# ATU_MCU.net
KiCad netlist of a schematic drawn in Altium Designer
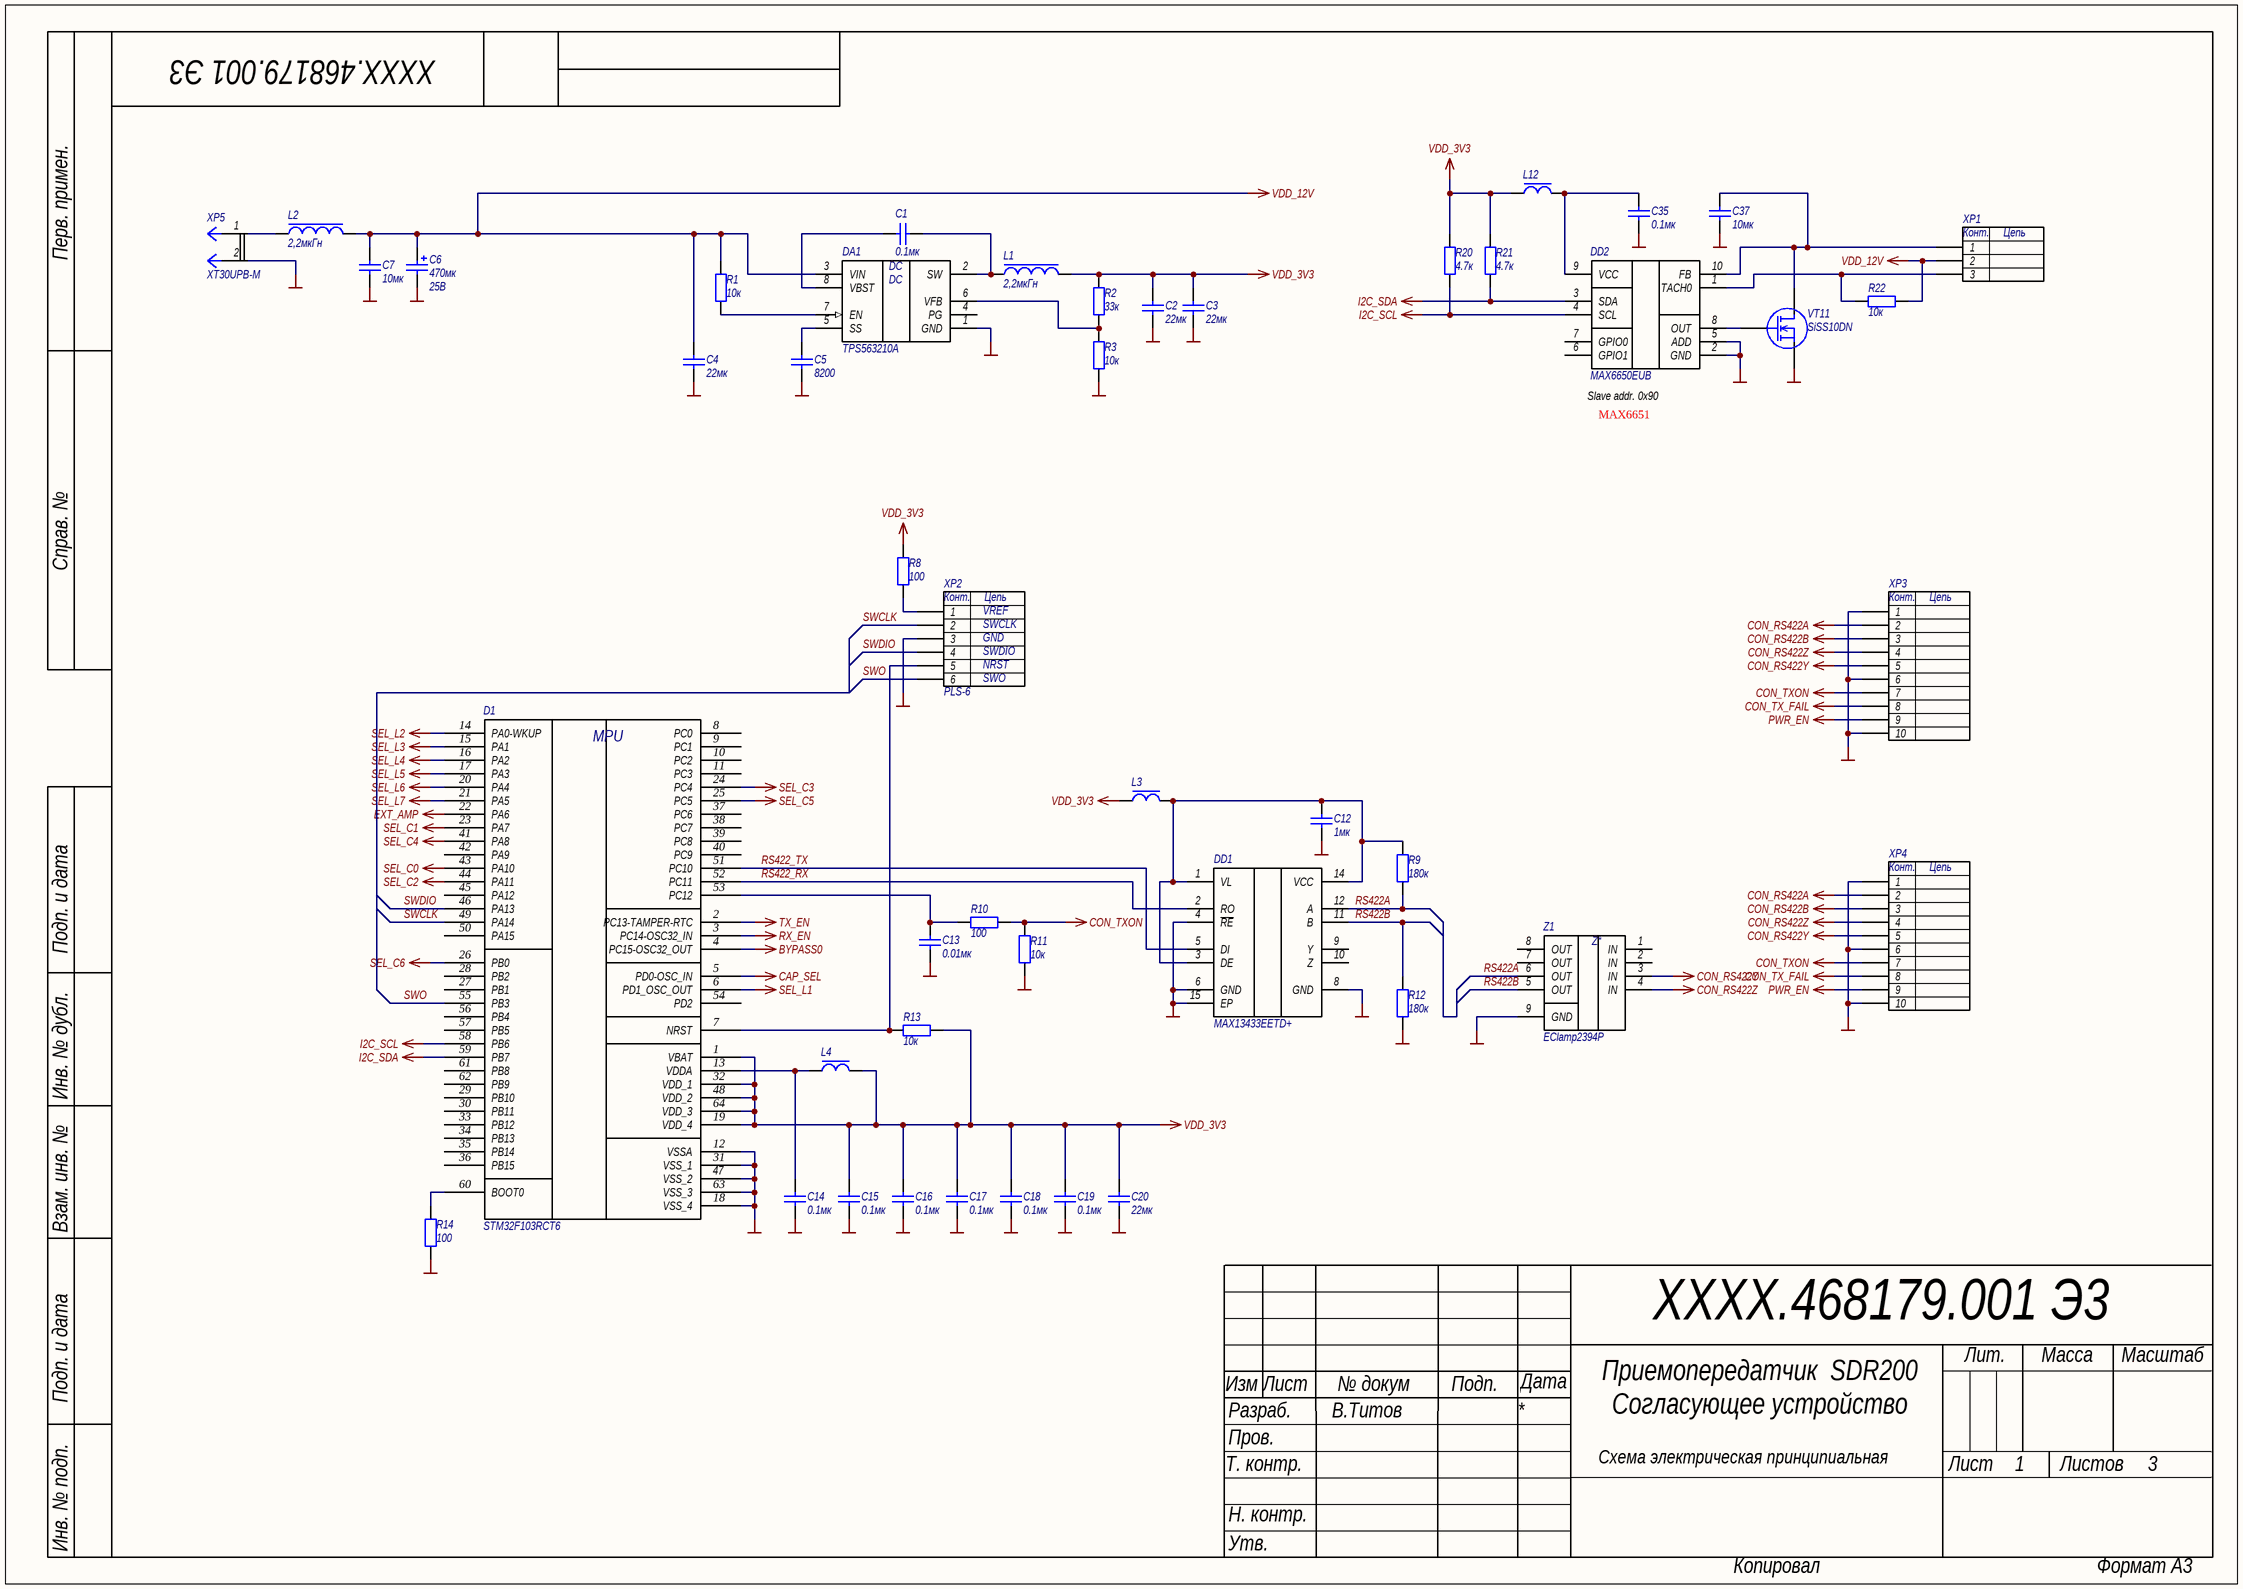
[diagram p0: ATU_MCU.SchDoc]

(export (version "E")
  (design (tool "Eeschema 10.0.6"))
  (components
    (comp (ref "C1")
      (value "0.1мк")
      (footprint "CAPC1005X06N")
      (description "Кер. ЧИП-конденсатор")
      (fields (field (name "TOLERANCE") "±10%"))
      (libsource (lib "nels") (part "Кер.ЧИП конд. 0402 0.1мкФ X7R 10%, 16В"))
    )
    (comp (ref "C2")
      (value "22мк")
      (footprint "CAPC2012X12L")
      (description "Кер. ЧИП-конденсатор")
      (fields (field (name "MANUFACTURER") "TDK") (field (name "TOLERANCE") "±10%"))
      (libsource (lib "nels_caps") (part "Кер.ЧИП конд. 0805 22мкФ X5R 10% 16В"))
    )
    (comp (ref "C3")
      (value "22мк")
      (footprint "CAPC2012X12L")
      (description "Кер. ЧИП-конденсатор")
      (fields (field (name "MANUFACTURER") "TDK") (field (name "TOLERANCE") "±10%"))
      (libsource (lib "nels_caps") (part "Кер.ЧИП конд. 0805 22мкФ X5R 10% 16В"))
    )
    (comp (ref "C4")
      (value "22мк")
      (footprint "CAPC2012X12L")
      (description "Кер. ЧИП-конденсатор")
      (fields (field (name "MANUFACTURER") "TDK") (field (name "TOLERANCE") "±10%"))
      (libsource (lib "nels_caps") (part "Кер.ЧИП конд. 0805 22мкФ X5R 10% 16В"))
    )
    (comp (ref "C5")
      (value "8200")
      (footprint "CAPC1005X06N")
      (description "Кер. ЧИП-конденсатор")
      (fields (field (name "TOLERANCE") "±20%"))
      (libsource (lib "nels_caps") (part "Кер.ЧИП конд. 0402 8200пФ X7R 10%, 50В"))
    )
    (comp (ref "C6")
      (value "470мк")
      (footprint "CAPAE116103X105N")
      (description "Гибридный ЧИП-конденсатор")
      (fields
        (field (name "TOLERANCE") "±20%")
        (field (name "MANUFACTURERPARTNUMBER") "EEHZK1E471P")
        (field (name "POWER/VOLTAGE") "25В")
        (field (name "PUBLISHER") "Altium Limited")
      )
      (libsource (lib "nels_caps") (part "Конденсатор гибридный SMD 470мкФ ±20% 25В"))
    )
    (comp (ref "C7")
      (value "10мк")
      (footprint "CAPC3225X27L")
      (description "Кер. ЧИП-конденсатор")
      (fields (field (name "MANUFACTURER") "Murata") (field (name "TOLERANCE") "±20%"))
      (libsource (lib "nels_caps") (part "Кер.ЧИП конд. 1210 10мкФ X5R 20% 50В"))
    )
    (comp (ref "C12")
      (value "1мк")
      (footprint "CAPC1005X06N")
      (description "Кер. ЧИП-конденсатор")
      (fields (field (name "TOLERANCE") "±10%"))
      (libsource (lib "nels_caps") (part "Кер.ЧИП конд. 0402 1мкФ X5R 10%, 10В"))
    )
    (comp (ref "C13")
      (value "0.01мк")
      (footprint "CAPC1005X06N")
      (description "Кер. ЧИП-конденсатор")
      (fields (field (name "TOLERANCE") "±20%"))
      (libsource (lib "nels_caps") (part "Кер.ЧИП конд. 0402 0.01мкФ X7R 10%, 50В"))
    )
    (comp (ref "C14")
      (value "0.1мк")
      (footprint "CAPC1005X06N")
      (description "Кер. ЧИП-конденсатор")
      (fields (field (name "TOLERANCE") "±10%"))
      (libsource (lib "nels") (part "Кер.ЧИП конд. 0402 0.1мкФ X7R 10%, 16В"))
    )
    (comp (ref "C15")
      (value "0.1мк")
      (footprint "CAPC1005X06N")
      (description "Кер. ЧИП-конденсатор")
      (fields (field (name "TOLERANCE") "±10%"))
      (libsource (lib "nels") (part "Кер.ЧИП конд. 0402 0.1мкФ X7R 10%, 16В"))
    )
    (comp (ref "C16")
      (value "0.1мк")
      (footprint "CAPC1005X06N")
      (description "Кер. ЧИП-конденсатор")
      (fields (field (name "TOLERANCE") "±10%"))
      (libsource (lib "nels") (part "Кер.ЧИП конд. 0402 0.1мкФ X7R 10%, 16В"))
    )
    (comp (ref "C17")
      (value "0.1мк")
      (footprint "CAPC1005X06N")
      (description "Кер. ЧИП-конденсатор")
      (fields (field (name "TOLERANCE") "±10%"))
      (libsource (lib "nels") (part "Кер.ЧИП конд. 0402 0.1мкФ X7R 10%, 16В"))
    )
    (comp (ref "C18")
      (value "0.1мк")
      (footprint "CAPC1005X06N")
      (description "Кер. ЧИП-конденсатор")
      (fields (field (name "TOLERANCE") "±10%"))
      (libsource (lib "nels") (part "Кер.ЧИП конд. 0402 0.1мкФ X7R 10%, 16В"))
    )
    (comp (ref "C19")
      (value "0.1мк")
      (footprint "CAPC1005X06N")
      (description "Кер. ЧИП-конденсатор")
      (fields (field (name "TOLERANCE") "±10%"))
      (libsource (lib "nels") (part "Кер.ЧИП конд. 0402 0.1мкФ X7R 10%, 16В"))
    )
    (comp (ref "C20")
      (value "22мк")
      (footprint "CAPC2012X12L")
      (description "Кер. ЧИП-конденсатор")
      (fields (field (name "MANUFACTURER") "TDK") (field (name "TOLERANCE") "±10%"))
      (libsource (lib "nels_caps") (part "Кер.ЧИП конд. 0805 22мкФ X5R 10% 16В"))
    )
    (comp (ref "C35")
      (value "0.1мк")
      (footprint "CAPC1005X06N")
      (description "Кер. ЧИП-конденсатор")
      (fields (field (name "TOLERANCE") "±10%"))
      (libsource (lib "nels") (part "Кер.ЧИП конд. 0402 0.1мкФ X7R 10%, 16В"))
    )
    (comp (ref "C37")
      (value "10мк")
      (footprint "CAPC3225X27L")
      (description "Кер. ЧИП-конденсатор")
      (fields (field (name "MANUFACTURER") "Murata") (field (name "TOLERANCE") "±20%"))
      (libsource (lib "nels_caps") (part "Кер.ЧИП конд. 1210 10мкФ X5R 20% 50В"))
    )
    (comp (ref "D1")
      (value "STM32F103RCT6")
      (footprint "QFP50P1200X1200X160-64N")
      (fields (field (name "MANUFACTURER") "STMicroelectronics"))
      (libsource (lib "nels_chip") (part "Микросхема STM32F103RCT6"))
    )
    (comp (ref "DA1")
      (value "TPS563210A")
      (footprint "MB:TSOP65P280X110-8N")
      (description "TPS56x210A, 4.5-V to 17-V Input, 2-A, 3-A Synchrono")
      (fields (field (name "MANUFACTURER") "TI"))
      (libsource (lib "RF") (part "Микросхема TPS563210A"))
    )
    (comp (ref "DD1")
      (value "MAX13433EETD+")
      (footprint "SON40P300X80_HS-15L")
      (description "RS-422 Transceivers with Low-Voltage Logic Interface 16M")
      (fields (field (name "MANUFACTURER") "Maxim"))
      (libsource (lib "nels_chip") (part "Микросхема MAX13433EETD+"))
    )
    (comp (ref "DD2")
      (value "MAX6650EUB")
      (footprint "SOP64P600X175-16N")
      (description "Fan-Speed Regulators and Monitors with SMBus/I2C-Compatible Interface")
      (fields (field (name "MANUFACTURER") "Maxim"))
      (libsource (lib "nels_chip") (part "Микросхема MAX6650EUB"))
    )
    (comp (ref "L1")
      (value "2,2мкГн")
      (footprint "CSAB0420")
      (description "Molding Power Choke")
      (fields
        (field (name "MANUFACTURER") "Vishay")
        (field (name "MANUFACTURERPARTNUMBER") "IHLP1616ABER1R0M11")
      )
      (libsource (lib "nels_ind") (part "ЧИП индуктивность CSAB0420-2R2M"))
    )
    (comp (ref "L2")
      (value "2,2мкГн")
      (footprint "CSAB0420")
      (description "Molding Power Choke")
      (fields
        (field (name "MANUFACTURER") "Vishay")
        (field (name "MANUFACTURERPARTNUMBER") "IHLP1616ABER1R0M11")
      )
      (libsource (lib "nels_ind") (part "ЧИП индуктивность CSAB0420-2R2M"))
    )
    (comp (ref "L3")
      (value "BLM18PG121SN1D")
      (footprint "INDC1608X08L")
      (description "SMD EMI Suppression Filter EMIFIL")
      (fields (field (name "MANUFACTURER") "Murata"))
      (libsource (lib "nels_ind") (part "ЧИП дроссель 0603 BLM18PG121SN1D"))
    )
    (comp (ref "L4")
      (value "BLM18PG121SN1D")
      (footprint "INDC1608X08L")
      (description "SMD EMI Suppression Filter EMIFIL")
      (fields (field (name "MANUFACTURER") "Murata"))
      (libsource (lib "nels_ind") (part "ЧИП дроссель 0603 BLM18PG121SN1D"))
    )
    (comp (ref "L12")
      (value "BLM18PG121SN1D")
      (footprint "INDC1608X08L")
      (description "SMD EMI Suppression Filter EMIFIL")
      (fields (field (name "MANUFACTURER") "Murata"))
      (libsource (lib "nels_ind") (part "ЧИП дроссель 0603 BLM18PG121SN1D"))
    )
    (comp (ref "R1")
      (value "10к")
      (footprint "RESC1005X06N")
      (description "ЧИП-резистор")
      (fields (field (name "TOLERANCE") "±5%"))
      (libsource (lib "nels_res") (part "Чип резистор 0402 10 кОм, 1%"))
    )
    (comp (ref "R2")
      (value "33к")
      (footprint "RESC1005X06N")
      (description "ЧИП-резистор")
      (fields (field (name "TOLERANCE") "±5%"))
      (libsource (lib "nels_res") (part "Чип резистор 0402 33 кОм, 5%"))
    )
    (comp (ref "R3")
      (value "10к")
      (footprint "RESC1005X06N")
      (description "ЧИП-резистор")
      (fields (field (name "TOLERANCE") "±5%"))
      (libsource (lib "") (part "Чип резистор 0402 10 кОм, 5%_1"))
    )
    (comp (ref "R8")
      (value "100")
      (footprint "RESC1005X06N")
      (description "ЧИП-резистор")
      (fields (field (name "TOLERANCE") "±5%"))
      (libsource (lib "nels_res") (part "Чип резистор 0402 100 Ом, 5%"))
    )
    (comp (ref "R9")
      (value "180к")
      (footprint "RESC1005X06N")
      (description "ЧИП-резистор")
      (fields (field (name "TOLERANCE") "±5%"))
      (libsource (lib "nels") (part "Чип резистор 0402 180 кОм, 5%"))
    )
    (comp (ref "R10")
      (value "100")
      (footprint "RESC1005X06N")
      (description "ЧИП-резистор")
      (fields (field (name "TOLERANCE") "±5%"))
      (libsource (lib "") (part "Чип резистор 0402 100 Ом, 5%_1"))
    )
    (comp (ref "R11")
      (value "10к")
      (footprint "RESC1005X06N")
      (description "ЧИП-резистор")
      (fields (field (name "TOLERANCE") "±5%"))
      (libsource (lib "") (part "Чип резистор 0402 10 кОм, 5%_1"))
    )
    (comp (ref "R12")
      (value "180к")
      (footprint "RESC1005X06N")
      (description "ЧИП-резистор")
      (fields (field (name "TOLERANCE") "±5%"))
      (libsource (lib "nels") (part "Чип резистор 0402 180 кОм, 5%"))
    )
    (comp (ref "R13")
      (value "10к")
      (footprint "RESC1005X06N")
      (description "ЧИП-резистор")
      (fields (field (name "TOLERANCE") "±5%"))
      (libsource (lib "nels_res") (part "Чип резистор 0402 10 кОм, 5%"))
    )
    (comp (ref "R14")
      (value "100")
      (footprint "RESC1005X06N")
      (description "ЧИП-резистор")
      (fields (field (name "TOLERANCE") "±5%"))
      (libsource (lib "nels_res") (part "Чип резистор 0402 100 Ом, 5%"))
    )
    (comp (ref "R20")
      (value "4.7к")
      (footprint "RESC1005X06N")
      (description "ЧИП-резистор")
      (fields (field (name "TOLERANCE") "±5%"))
      (libsource (lib "nels_res") (part "Чип резистор 0402 4,7 кОм, 5%"))
    )
    (comp (ref "R21")
      (value "4.7к")
      (footprint "RESC1005X06N")
      (description "ЧИП-резистор")
      (fields (field (name "TOLERANCE") "±5%"))
      (libsource (lib "nels_res") (part "Чип резистор 0402 4,7 кОм, 5%"))
    )
    (comp (ref "R22")
      (value "10к")
      (footprint "RESC1005X06N")
      (description "ЧИП-резистор")
      (fields (field (name "TOLERANCE") "±5%"))
      (libsource (lib "nels_res") (part "Чип резистор 0402 10 кОм, 5%"))
    )
    (comp (ref "VT11")
      (value "SiSS10DN")
      (footprint "PowerPAK_1212-8W")
      (description "N-Channel 40 V (D-S) MOSFET")
      (libsource (lib "nels_other") (part "ЧИП транзистор SiSS10DN"))
    )
    (comp (ref "XP1")
      (value "22232031")
      (footprint "22232031")
      (description "Molex 2,54 мм pitch-3")
      (fields (field (name "MANUFACTURER") "Connfly"))
      (libsource (lib "nels_conn") (part "Соединитель 22232031"))
    )
    (comp (ref "XP2")
      (value "PLS-6")
      (footprint "HDR1X6")
      (description "Вилка штыревая 2.54мм 1x6 прямая тип1")
      (fields (field (name "PUBLISHER") "Altium Limited"))
      (libsource (lib "nels_conn") (part "Соединитель PLS-6"))
    )
    (comp (ref "XP3")
      (value "FH12-10S-0.5SVA")
      (footprint "FH12-10S-0.5SH")
      (description "0.5mm  Pitch FPC/FFC Connector FH12 Series")
      (fields (field (name "MANUFACTURER") "Hirose"))
      (libsource (lib "nels_conn") (part "Соединитель FH12-10S-0.5SVA"))
    )
    (comp (ref "XP4")
      (value "FH12-10S-0.5SVA")
      (footprint "FH12-10S-0.5SH")
      (description "0.5mm  Pitch FPC/FFC Connector FH12 Series")
      (fields (field (name "MANUFACTURER") "Hirose"))
      (libsource (lib "nels_conn") (part "Соединитель FH12-10S-0.5SVA"))
    )
    (comp (ref "XP5")
      (value "XT30UPB-M")
      (footprint "XT30UPB-M")
      (description "AMASS XT30UPB-M  5 mm")
      (libsource (lib "nels_conn") (part "Соединитель XT30UPB-M"))
    )
    (comp (ref "Z1")
      (value "EClamp2394P")
      (footprint "SON50P160X65_HS-9N")
      (description "ESD/EMI Protection  for Color LCD Interfaces")
      (fields (field (name "MANUFACTURER") "SEMTECH"))
      (libsource (lib "nels_other") (part "Фильтр EMI EClamp2394P"))
    )
  )
  (nets
    (net (code "1") (name "/RS422A") (class "Default")
      (node (ref "DD1") (pin "12") (pinfunction "A_12") (pintype "passive"))
      (node (ref "R9") (pin "1") (pinfunction "1_1") (pintype "passive"))
      (node (ref "Z1") (pin "6") (pinfunction "OUT_6") (pintype "passive"))
    )
    (net (code "2") (name "/RS422B") (class "Default")
      (node (ref "DD1") (pin "11") (pinfunction "B_11") (pintype "passive"))
      (node (ref "R12") (pin "2") (pinfunction "2_2") (pintype "passive"))
      (node (ref "Z1") (pin "5") (pinfunction "OUT_5") (pintype "passive"))
    )
    (net (code "3") (name "/RS422_RX") (class "Default")
      (node (ref "D1") (pin "52") (pinfunction "PC11_52") (pintype "passive"))
      (node (ref "DD1") (pin "2") (pinfunction "RO_2") (pintype "passive"))
    )
    (net (code "4") (name "/RS422_TX") (class "Default")
      (node (ref "D1") (pin "51") (pinfunction "PC10_51") (pintype "passive"))
      (node (ref "DD1") (pin "5") (pinfunction "DI_5") (pintype "passive"))
    )
    (net (code "5") (name "/SWCLK") (class "Default")
      (node (ref "D1") (pin "49") (pinfunction "PA14_49") (pintype "passive"))
      (node (ref "XP2") (pin "2") (pinfunction "2_2") (pintype "passive"))
    )
    (net (code "6") (name "/SWDIO") (class "Default")
      (node (ref "D1") (pin "46") (pinfunction "PA13_46") (pintype "passive"))
      (node (ref "XP2") (pin "4") (pinfunction "4_4") (pintype "passive"))
    )
    (net (code "7") (name "/SWO") (class "Default")
      (node (ref "D1") (pin "55") (pinfunction "PB3_55") (pintype "passive"))
      (node (ref "XP2") (pin "6") (pinfunction "6_6") (pintype "passive"))
    )
    (net (code "8") (name "BYPASS0") (class "Default")
      (node (ref "D1") (pin "4") (pinfunction "PC15-OSC32_OUT_4") (pintype "passive"))
    )
    (net (code "9") (name "CAP_SEL") (class "Default")
      (node (ref "D1") (pin "5") (pinfunction "PD0-OSC_IN_5") (pintype "passive"))
    )
    (net (code "10") (name "CON_RS422A") (class "Default")
      (node (ref "XP3") (pin "2") (pinfunction "2_2") (pintype "passive"))
      (node (ref "XP4") (pin "2") (pinfunction "2_2") (pintype "passive"))
    )
    (net (code "11") (name "CON_RS422B") (class "Default")
      (node (ref "XP3") (pin "3") (pinfunction "3_3") (pintype "passive"))
      (node (ref "XP4") (pin "3") (pinfunction "3_3") (pintype "passive"))
    )
    (net (code "12") (name "CON_RS422Y") (class "Default")
      (node (ref "XP3") (pin "5") (pinfunction "5_5") (pintype "passive"))
      (node (ref "XP4") (pin "5") (pinfunction "5_5") (pintype "passive"))
      (node (ref "Z1") (pin "3") (pinfunction "IN_3") (pintype "passive"))
    )
    (net (code "13") (name "CON_RS422Z") (class "Default")
      (node (ref "XP3") (pin "4") (pinfunction "4_4") (pintype "passive"))
      (node (ref "XP4") (pin "4") (pinfunction "4_4") (pintype "passive"))
      (node (ref "Z1") (pin "4") (pinfunction "IN_4") (pintype "passive"))
    )
    (net (code "14") (name "CON_TXON") (class "Default")
      (node (ref "R10") (pin "1") (pinfunction "1_1") (pintype "passive"))
      (node (ref "R11") (pin "1") (pinfunction "1_1") (pintype "passive"))
      (node (ref "XP3") (pin "7") (pinfunction "7_7") (pintype "passive"))
      (node (ref "XP4") (pin "7") (pinfunction "7_7") (pintype "passive"))
    )
    (net (code "15") (name "CON_TX_FAIL") (class "Default")
      (node (ref "XP3") (pin "8") (pinfunction "8_8") (pintype "passive"))
      (node (ref "XP4") (pin "8") (pinfunction "8_8") (pintype "passive"))
    )
    (net (code "16") (name "EXT_AMP") (class "Default")
      (node (ref "D1") (pin "22") (pinfunction "PA6_22") (pintype "passive"))
    )
    (net (code "17") (name "GND") (class "Default")
      (node (ref "C12") (pin "1") (pinfunction "1_1") (pintype "passive"))
      (node (ref "C13") (pin "1") (pinfunction "1_1") (pintype "passive"))
      (node (ref "C14") (pin "1") (pinfunction "1_1") (pintype "passive"))
      (node (ref "C15") (pin "1") (pinfunction "1_1") (pintype "passive"))
      (node (ref "C16") (pin "1") (pinfunction "1_1") (pintype "passive"))
      (node (ref "C17") (pin "1") (pinfunction "1_1") (pintype "passive"))
      (node (ref "C18") (pin "1") (pinfunction "1_1") (pintype "passive"))
      (node (ref "C19") (pin "1") (pinfunction "1_1") (pintype "passive"))
      (node (ref "C2") (pin "1") (pinfunction "1_1") (pintype "passive"))
      (node (ref "C20") (pin "1") (pinfunction "1_1") (pintype "passive"))
      (node (ref "C3") (pin "1") (pinfunction "1_1") (pintype "passive"))
      (node (ref "C35") (pin "1") (pinfunction "1_1") (pintype "passive"))
      (node (ref "C37") (pin "1") (pinfunction "1_1") (pintype "passive"))
      (node (ref "C4") (pin "1") (pinfunction "1_1") (pintype "passive"))
      (node (ref "C5") (pin "1") (pinfunction "1_1") (pintype "passive"))
      (node (ref "C6") (pin "2") (pinfunction "2_2") (pintype "passive"))
      (node (ref "C7") (pin "1") (pinfunction "1_1") (pintype "passive"))
      (node (ref "D1") (pin "12") (pinfunction "VSSA_12") (pintype "passive"))
      (node (ref "D1") (pin "18") (pinfunction "VSS_4_18") (pintype "passive"))
      (node (ref "D1") (pin "31") (pinfunction "VSS_1_31") (pintype "passive"))
      (node (ref "D1") (pin "47") (pinfunction "VSS_2_47") (pintype "passive"))
      (node (ref "D1") (pin "63") (pinfunction "VSS_3_63") (pintype "passive"))
      (node (ref "DA1") (pin "1") (pinfunction "GND_1") (pintype "passive"))
      (node (ref "DD1") (pin "15") (pinfunction "EP_15") (pintype "passive"))
      (node (ref "DD1") (pin "4") (pinfunction "~{RE}_4") (pintype "passive"))
      (node (ref "DD1") (pin "6") (pinfunction "GND_6") (pintype "passive"))
      (node (ref "DD1") (pin "8") (pinfunction "GND_8") (pintype "passive"))
      (node (ref "DD2") (pin "2") (pinfunction "GND_2") (pintype "passive"))
      (node (ref "DD2") (pin "5") (pinfunction "ADD_5") (pintype "passive"))
      (node (ref "R11") (pin "2") (pinfunction "2_2") (pintype "passive"))
      (node (ref "R12") (pin "1") (pinfunction "1_1") (pintype "passive"))
      (node (ref "R14") (pin "2") (pinfunction "2_2") (pintype "passive"))
      (node (ref "R3") (pin "2") (pinfunction "2_2") (pintype "passive"))
      (node (ref "VT11") (pin "S") (pinfunction "S_S") (pintype "passive"))
      (node (ref "XP2") (pin "3") (pinfunction "3_3") (pintype "passive"))
      (node (ref "XP3") (pin "1") (pinfunction "1_1") (pintype "passive"))
      (node (ref "XP3") (pin "10") (pinfunction "10_10") (pintype "passive"))
      (node (ref "XP3") (pin "6") (pinfunction "6_6") (pintype "passive"))
      (node (ref "XP4") (pin "1") (pinfunction "1_1") (pintype "passive"))
      (node (ref "XP4") (pin "10") (pinfunction "10_10") (pintype "passive"))
      (node (ref "XP4") (pin "6") (pinfunction "6_6") (pintype "passive"))
      (node (ref "XP5") (pin "2") (pinfunction "~_2") (pintype "passive"))
      (node (ref "Z1") (pin "9") (pinfunction "GND_9") (pintype "passive"))
    )
    (net (code "18") (name "I2C_SCL") (class "Default")
      (node (ref "D1") (pin "58") (pinfunction "PB6_58") (pintype "passive"))
      (node (ref "DD2") (pin "4") (pinfunction "SCL_4") (pintype "passive"))
      (node (ref "R20") (pin "1") (pinfunction "1_1") (pintype "passive"))
    )
    (net (code "19") (name "I2C_SDA") (class "Default")
      (node (ref "D1") (pin "59") (pinfunction "PB7_59") (pintype "passive"))
      (node (ref "DD2") (pin "3") (pinfunction "SDA_3") (pintype "passive"))
      (node (ref "R21") (pin "1") (pinfunction "1_1") (pintype "passive"))
    )
    (net (code "20") (name "Net-(D1-BOOT0)") (class "Default")
      (node (ref "D1") (pin "60") (pinfunction "BOOT0_60") (pintype "passive"))
      (node (ref "R14") (pin "1") (pinfunction "1_1") (pintype "passive"))
    )
    (net (code "21") (name "Net-(D1-NRST)") (class "Default")
      (node (ref "D1") (pin "7") (pinfunction "NRST_7") (pintype "passive"))
      (node (ref "R13") (pin "1") (pinfunction "1_1") (pintype "passive"))
      (node (ref "XP2") (pin "5") (pinfunction "5_5") (pintype "passive"))
    )
    (net (code "22") (name "Net-(D1-PC12)") (class "Default")
      (node (ref "C13") (pin "2") (pinfunction "2_2") (pintype "passive"))
      (node (ref "D1") (pin "53") (pinfunction "PC12_53") (pintype "passive"))
      (node (ref "R10") (pin "2") (pinfunction "2_2") (pintype "passive"))
    )
    (net (code "23") (name "Net-(D1-VDDA)") (class "Default")
      (node (ref "C14") (pin "2") (pinfunction "2_2") (pintype "passive"))
      (node (ref "D1") (pin "13") (pinfunction "VDDA_13") (pintype "passive"))
      (node (ref "L4") (pin "1") (pinfunction "1_1") (pintype "passive"))
    )
    (net (code "24") (name "Net-(DA1-EN)") (class "Default")
      (node (ref "DA1") (pin "7") (pinfunction "EN_7") (pintype "input"))
      (node (ref "R1") (pin "1") (pinfunction "1_1") (pintype "passive"))
    )
    (net (code "25") (name "Net-(DA1-SS)") (class "Default")
      (node (ref "C5") (pin "2") (pinfunction "2_2") (pintype "passive"))
      (node (ref "DA1") (pin "5") (pinfunction "SS_5") (pintype "passive"))
    )
    (net (code "26") (name "Net-(DA1-SW)") (class "Default")
      (node (ref "C1") (pin "1") (pinfunction "1_1") (pintype "passive"))
      (node (ref "DA1") (pin "2") (pinfunction "SW_2") (pintype "passive"))
      (node (ref "L1") (pin "1") (pinfunction "1_1") (pintype "passive"))
    )
    (net (code "27") (name "Net-(DA1-VBST)") (class "Default")
      (node (ref "C1") (pin "2") (pinfunction "2_2") (pintype "passive"))
      (node (ref "DA1") (pin "8") (pinfunction "VBST_8") (pintype "passive"))
    )
    (net (code "28") (name "Net-(DA1-VFB)") (class "Default")
      (node (ref "DA1") (pin "6") (pinfunction "VFB_6") (pintype "passive"))
      (node (ref "R2") (pin "1") (pinfunction "1_1") (pintype "passive"))
      (node (ref "R3") (pin "1") (pinfunction "1_1") (pintype "passive"))
    )
    (net (code "29") (name "Net-(DD1-DE)") (class "Default")
      (node (ref "C12") (pin "2") (pinfunction "2_2") (pintype "passive"))
      (node (ref "DD1") (pin "1") (pinfunction "VL_1") (pintype "passive"))
      (node (ref "DD1") (pin "14") (pinfunction "VCC_14") (pintype "passive"))
      (node (ref "DD1") (pin "3") (pinfunction "DE_3") (pintype "passive"))
      (node (ref "L3") (pin "2") (pinfunction "2_2") (pintype "passive"))
      (node (ref "R9") (pin "2") (pinfunction "2_2") (pintype "passive"))
    )
    (net (code "30") (name "Net-(DD2-FB)") (class "Default")
      (node (ref "C37") (pin "2") (pinfunction "2_2") (pintype "passive"))
      (node (ref "DD2") (pin "10") (pinfunction "FB_10") (pintype "passive"))
      (node (ref "VT11") (pin "D") (pinfunction "D_D") (pintype "passive"))
      (node (ref "XP1") (pin "1") (pinfunction "1_1") (pintype "passive"))
    )
    (net (code "31") (name "Net-(DD2-OUT)") (class "Default")
      (node (ref "DD2") (pin "8") (pinfunction "OUT_8") (pintype "passive"))
      (node (ref "VT11") (pin "G") (pinfunction "G_G") (pintype "passive"))
    )
    (net (code "32") (name "Net-(DD2-TACH0)") (class "Default")
      (node (ref "DD2") (pin "1") (pinfunction "TACH0_1") (pintype "passive"))
      (node (ref "R22") (pin "1") (pinfunction "1_1") (pintype "passive"))
      (node (ref "XP1") (pin "3") (pinfunction "3_3") (pintype "passive"))
    )
    (net (code "33") (name "Net-(DD2-VCC)") (class "Default")
      (node (ref "C35") (pin "2") (pinfunction "2_2") (pintype "passive"))
      (node (ref "DD2") (pin "9") (pinfunction "VCC_9") (pintype "passive"))
      (node (ref "L12") (pin "2") (pinfunction "2_2") (pintype "passive"))
    )
    (net (code "34") (name "Net-(L2-Pad1)") (class "Default")
      (node (ref "L2") (pin "1") (pinfunction "1_1") (pintype "passive"))
      (node (ref "XP5") (pin "1") (pinfunction "~_1") (pintype "passive"))
    )
    (net (code "35") (name "Net-(R8-Pad2)") (class "Default")
      (node (ref "R8") (pin "2") (pinfunction "2_2") (pintype "passive"))
      (node (ref "XP2") (pin "1") (pinfunction "1_1") (pintype "passive"))
    )
    (net (code "36") (name "PWR_EN") (class "Default")
      (node (ref "XP3") (pin "9") (pinfunction "9_9") (pintype "passive"))
      (node (ref "XP4") (pin "9") (pinfunction "9_9") (pintype "passive"))
    )
    (net (code "37") (name "RX_EN") (class "Default")
      (node (ref "D1") (pin "3") (pinfunction "PC14-OSC32_IN_3") (pintype "passive"))
    )
    (net (code "38") (name "SEL_C0") (class "Default")
      (node (ref "D1") (pin "43") (pinfunction "PA10_43") (pintype "passive"))
    )
    (net (code "39") (name "SEL_C1") (class "Default")
      (node (ref "D1") (pin "23") (pinfunction "PA7_23") (pintype "passive"))
    )
    (net (code "40") (name "SEL_C2") (class "Default")
      (node (ref "D1") (pin "44") (pinfunction "PA11_44") (pintype "passive"))
    )
    (net (code "41") (name "SEL_C3") (class "Default")
      (node (ref "D1") (pin "24") (pinfunction "PC4_24") (pintype "passive"))
    )
    (net (code "42") (name "SEL_C4") (class "Default")
      (node (ref "D1") (pin "41") (pinfunction "PA8_41") (pintype "passive"))
    )
    (net (code "43") (name "SEL_C5") (class "Default")
      (node (ref "D1") (pin "25") (pinfunction "PC5_25") (pintype "passive"))
    )
    (net (code "44") (name "SEL_C6") (class "Default")
      (node (ref "D1") (pin "26") (pinfunction "PB0_26") (pintype "passive"))
    )
    (net (code "45") (name "SEL_L1") (class "Default")
      (node (ref "D1") (pin "6") (pinfunction "PD1_OSC_OUT_6") (pintype "passive"))
    )
    (net (code "46") (name "SEL_L2") (class "Default")
      (node (ref "D1") (pin "14") (pinfunction "PA0-WKUP_14") (pintype "passive"))
    )
    (net (code "47") (name "SEL_L3") (class "Default")
      (node (ref "D1") (pin "15") (pinfunction "PA1_15") (pintype "passive"))
    )
    (net (code "48") (name "SEL_L4") (class "Default")
      (node (ref "D1") (pin "16") (pinfunction "PA2_16") (pintype "passive"))
    )
    (net (code "49") (name "SEL_L5") (class "Default")
      (node (ref "D1") (pin "17") (pinfunction "PA3_17") (pintype "passive"))
    )
    (net (code "50") (name "SEL_L6") (class "Default")
      (node (ref "D1") (pin "20") (pinfunction "PA4_20") (pintype "passive"))
    )
    (net (code "51") (name "SEL_L7") (class "Default")
      (node (ref "D1") (pin "21") (pinfunction "PA5_21") (pintype "passive"))
    )
    (net (code "52") (name "TX_EN") (class "Default")
      (node (ref "D1") (pin "2") (pinfunction "PC13-TAMPER-RTC_2") (pintype "passive"))
    )
    (net (code "53") (name "VDD_3V3") (class "Default")
      (node (ref "C15") (pin "2") (pinfunction "2_2") (pintype "passive"))
      (node (ref "C16") (pin "2") (pinfunction "2_2") (pintype "passive"))
      (node (ref "C17") (pin "2") (pinfunction "2_2") (pintype "passive"))
      (node (ref "C18") (pin "2") (pinfunction "2_2") (pintype "passive"))
      (node (ref "C19") (pin "2") (pinfunction "2_2") (pintype "passive"))
      (node (ref "C2") (pin "2") (pinfunction "2_2") (pintype "passive"))
      (node (ref "C20") (pin "2") (pinfunction "2_2") (pintype "passive"))
      (node (ref "C3") (pin "2") (pinfunction "2_2") (pintype "passive"))
      (node (ref "D1") (pin "1") (pinfunction "VBAT_1") (pintype "passive"))
      (node (ref "D1") (pin "19") (pinfunction "VDD_4_19") (pintype "passive"))
      (node (ref "D1") (pin "32") (pinfunction "VDD_1_32") (pintype "passive"))
      (node (ref "D1") (pin "48") (pinfunction "VDD_2_48") (pintype "passive"))
      (node (ref "D1") (pin "64") (pinfunction "VDD_3_64") (pintype "passive"))
      (node (ref "L1") (pin "2") (pinfunction "2_2") (pintype "passive"))
      (node (ref "L12") (pin "1") (pinfunction "1_1") (pintype "passive"))
      (node (ref "L3") (pin "1") (pinfunction "1_1") (pintype "passive"))
      (node (ref "L4") (pin "2") (pinfunction "2_2") (pintype "passive"))
      (node (ref "R13") (pin "2") (pinfunction "2_2") (pintype "passive"))
      (node (ref "R2") (pin "2") (pinfunction "2_2") (pintype "passive"))
      (node (ref "R20") (pin "2") (pinfunction "2_2") (pintype "passive"))
      (node (ref "R21") (pin "2") (pinfunction "2_2") (pintype "passive"))
      (node (ref "R8") (pin "1") (pinfunction "1_1") (pintype "passive"))
    )
    (net (code "54") (name "VDD_12V") (class "Default")
      (node (ref "C4") (pin "2") (pinfunction "2_2") (pintype "passive"))
      (node (ref "C6") (pin "1") (pinfunction "1_1") (pintype "passive"))
      (node (ref "C7") (pin "2") (pinfunction "2_2") (pintype "passive"))
      (node (ref "DA1") (pin "3") (pinfunction "VIN_3") (pintype "passive"))
      (node (ref "L2") (pin "2") (pinfunction "2_2") (pintype "passive"))
      (node (ref "R1") (pin "2") (pinfunction "2_2") (pintype "passive"))
      (node (ref "R22") (pin "2") (pinfunction "2_2") (pintype "passive"))
      (node (ref "XP1") (pin "2") (pinfunction "2_2") (pintype "passive"))
    )
    (net (code "55") (name "unconnected-(D1-PA9-Pad42)") (class "Default")
      (node (ref "D1") (pin "42") (pinfunction "PA9_42") (pintype "passive"))
    )
    (net (code "56") (name "unconnected-(D1-PA12-Pad45)") (class "Default")
      (node (ref "D1") (pin "45") (pinfunction "PA12_45") (pintype "passive"))
    )
    (net (code "57") (name "unconnected-(D1-PA15-Pad50)") (class "Default")
      (node (ref "D1") (pin "50") (pinfunction "PA15_50") (pintype "passive"))
    )
    (net (code "58") (name "unconnected-(D1-PB1-Pad27)") (class "Default")
      (node (ref "D1") (pin "27") (pinfunction "PB1_27") (pintype "passive"))
    )
    (net (code "59") (name "unconnected-(D1-PB2-Pad28)") (class "Default")
      (node (ref "D1") (pin "28") (pinfunction "PB2_28") (pintype "passive"))
    )
    (net (code "60") (name "unconnected-(D1-PB4-Pad56)") (class "Default")
      (node (ref "D1") (pin "56") (pinfunction "PB4_56") (pintype "passive"))
    )
    (net (code "61") (name "unconnected-(D1-PB5-Pad57)") (class "Default")
      (node (ref "D1") (pin "57") (pinfunction "PB5_57") (pintype "passive"))
    )
    (net (code "62") (name "unconnected-(D1-PB8-Pad61)") (class "Default")
      (node (ref "D1") (pin "61") (pinfunction "PB8_61") (pintype "passive"))
    )
    (net (code "63") (name "unconnected-(D1-PB9-Pad62)") (class "Default")
      (node (ref "D1") (pin "62") (pinfunction "PB9_62") (pintype "passive"))
    )
    (net (code "64") (name "unconnected-(D1-PB10-Pad29)") (class "Default")
      (node (ref "D1") (pin "29") (pinfunction "PB10_29") (pintype "passive"))
    )
    (net (code "65") (name "unconnected-(D1-PB11-Pad30)") (class "Default")
      (node (ref "D1") (pin "30") (pinfunction "PB11_30") (pintype "passive"))
    )
    (net (code "66") (name "unconnected-(D1-PB12-Pad33)") (class "Default")
      (node (ref "D1") (pin "33") (pinfunction "PB12_33") (pintype "passive"))
    )
    (net (code "67") (name "unconnected-(D1-PB13-Pad34)") (class "Default")
      (node (ref "D1") (pin "34") (pinfunction "PB13_34") (pintype "passive"))
    )
    (net (code "68") (name "unconnected-(D1-PB14-Pad35)") (class "Default")
      (node (ref "D1") (pin "35") (pinfunction "PB14_35") (pintype "passive"))
    )
    (net (code "69") (name "unconnected-(D1-PB15-Pad36)") (class "Default")
      (node (ref "D1") (pin "36") (pinfunction "PB15_36") (pintype "passive"))
    )
    (net (code "70") (name "unconnected-(D1-PC0-Pad8)") (class "Default")
      (node (ref "D1") (pin "8") (pinfunction "PC0_8") (pintype "passive"))
    )
    (net (code "71") (name "unconnected-(D1-PC1-Pad9)") (class "Default")
      (node (ref "D1") (pin "9") (pinfunction "PC1_9") (pintype "passive"))
    )
    (net (code "72") (name "unconnected-(D1-PC2-Pad10)") (class "Default")
      (node (ref "D1") (pin "10") (pinfunction "PC2_10") (pintype "passive"))
    )
    (net (code "73") (name "unconnected-(D1-PC3-Pad11)") (class "Default")
      (node (ref "D1") (pin "11") (pinfunction "PC3_11") (pintype "passive"))
    )
    (net (code "74") (name "unconnected-(D1-PC6-Pad37)") (class "Default")
      (node (ref "D1") (pin "37") (pinfunction "PC6_37") (pintype "passive"))
    )
    (net (code "75") (name "unconnected-(D1-PC7-Pad38)") (class "Default")
      (node (ref "D1") (pin "38") (pinfunction "PC7_38") (pintype "passive"))
    )
    (net (code "76") (name "unconnected-(D1-PC8-Pad39)") (class "Default")
      (node (ref "D1") (pin "39") (pinfunction "PC8_39") (pintype "passive"))
    )
    (net (code "77") (name "unconnected-(D1-PC9-Pad40)") (class "Default")
      (node (ref "D1") (pin "40") (pinfunction "PC9_40") (pintype "passive"))
    )
    (net (code "78") (name "unconnected-(D1-PD2-Pad54)") (class "Default")
      (node (ref "D1") (pin "54") (pinfunction "PD2_54") (pintype "passive"))
    )
    (net (code "79") (name "unconnected-(DA1-PG-Pad4)") (class "Default")
      (node (ref "DA1") (pin "4") (pinfunction "PG_4") (pintype "open_collector"))
    )
    (net (code "80") (name "unconnected-(DD1-Y-Pad9)") (class "Default")
      (node (ref "DD1") (pin "9") (pinfunction "Y_9") (pintype "passive"))
    )
    (net (code "81") (name "unconnected-(DD1-Z-Pad10)") (class "Default")
      (node (ref "DD1") (pin "10") (pinfunction "Z_10") (pintype "passive"))
    )
    (net (code "82") (name "unconnected-(DD2-GPIO0-Pad7)") (class "Default")
      (node (ref "DD2") (pin "7") (pinfunction "GPIO0_7") (pintype "passive"))
    )
    (net (code "83") (name "unconnected-(DD2-GPIO1-Pad6)") (class "Default")
      (node (ref "DD2") (pin "6") (pinfunction "GPIO1_6") (pintype "passive"))
    )
    (net (code "84") (name "unconnected-(Z1-IN-Pad1)") (class "Default")
      (node (ref "Z1") (pin "1") (pinfunction "IN_1") (pintype "passive"))
    )
    (net (code "85") (name "unconnected-(Z1-IN-Pad2)") (class "Default")
      (node (ref "Z1") (pin "2") (pinfunction "IN_2") (pintype "passive"))
    )
    (net (code "86") (name "unconnected-(Z1-OUT-Pad7)") (class "Default")
      (node (ref "Z1") (pin "7") (pinfunction "OUT_7") (pintype "passive"))
    )
    (net (code "87") (name "unconnected-(Z1-OUT-Pad8)") (class "Default")
      (node (ref "Z1") (pin "8") (pinfunction "OUT_8") (pintype "passive"))
    )
  )
)
